# PC.net
KiCad netlist of a schematic drawn in EAGLE
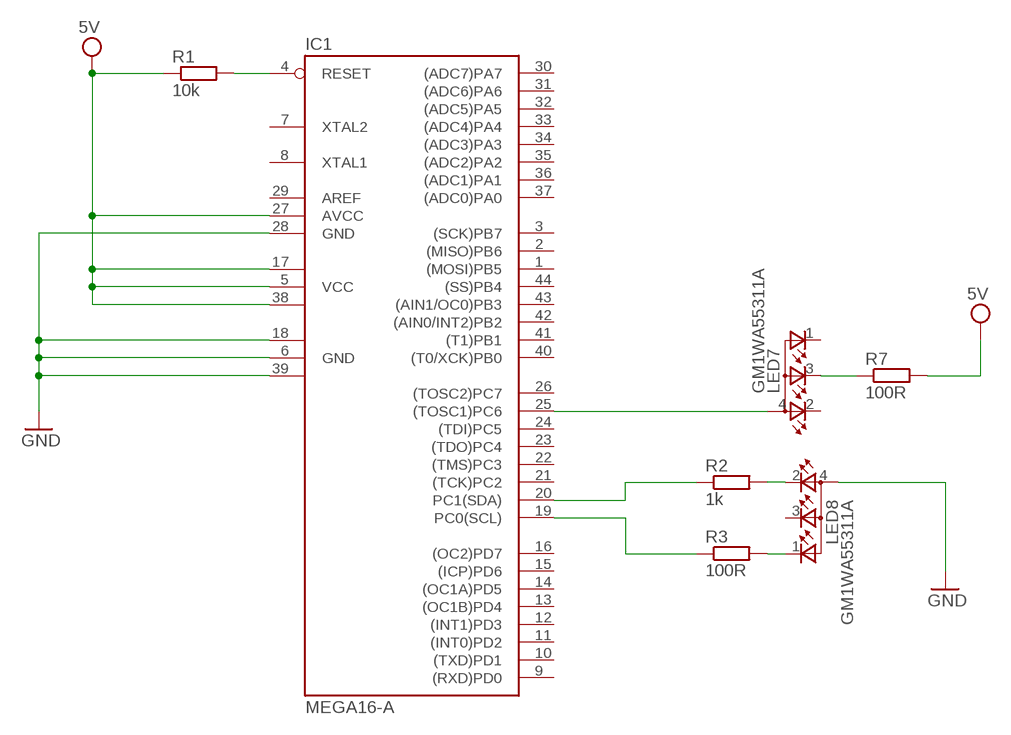
[diagram p0: schematic, sheet 1]

(export (version "E")
  (design (tool "Eeschema 10.0.6"))
  (components
    (comp (ref "IC1")
      (value "MEGA16-A")
      (footprint "eagle-import:TQFP44")
      (fields (field (name "MPN") "ATMEGA16-16AU"))
      (libsource (lib "eagle-import") (part "MEGA16-A"))
    )
    (comp (ref "LED7")
      (value "GM1WA55311A")
      (footprint "eagle-import:GM1WA55311A")
      (libsource (lib "eagle-import") (part "GM1WA55311A"))
    )
    (comp (ref "LED8")
      (value "GM1WA55311A")
      (footprint "eagle-import:GM1WA55311A")
      (libsource (lib "eagle-import") (part "GM1WA55311A"))
    )
    (comp (ref "R1")
      (value "10k")
      (footprint "eagle-import:M0805")
      (libsource (lib "eagle-import") (part "R-EU_M0805"))
    )
    (comp (ref "R2")
      (value "1k")
      (footprint "eagle-import:M0805")
      (libsource (lib "eagle-import") (part "R-EU_M0805"))
    )
    (comp (ref "R3")
      (value "100R")
      (footprint "eagle-import:M0805")
      (libsource (lib "eagle-import") (part "R-EU_M0805"))
    )
    (comp (ref "R7")
      (value "100R")
      (footprint "eagle-import:M0805")
      (libsource (lib "eagle-import") (part "R-EU_M0805"))
    )
  )
  (nets
    (net (code "1") (name "5V") (class "Default")
      (node (ref "IC1") (pin "17") (pinfunction "VCC1_17") (pintype "power_in"))
      (node (ref "IC1") (pin "27") (pinfunction "AVCC_27") (pintype "power_in"))
      (node (ref "IC1") (pin "38") (pinfunction "VCC2_38") (pintype "power_in"))
      (node (ref "IC1") (pin "5") (pinfunction "VCC_5") (pintype "power_in"))
      (node (ref "R1") (pin "1") (pinfunction "1_1") (pintype "passive"))
      (node (ref "R7") (pin "2") (pinfunction "2_2") (pintype "passive"))
    )
    (net (code "2") (name "GND") (class "Default")
      (node (ref "IC1") (pin "18") (pinfunction "GND1_18") (pintype "power_in"))
      (node (ref "IC1") (pin "28") (pinfunction "GND_28") (pintype "power_in"))
      (node (ref "IC1") (pin "39") (pinfunction "GND2_39") (pintype "power_in"))
      (node (ref "IC1") (pin "6") (pinfunction "GND_6") (pintype "power_in"))
    )
    (net (code "3") (name "Net-(IC1-(TOSC1)PC6)") (class "Default")
      (node (ref "IC1") (pin "25") (pinfunction "(TOSC1)PC6_25") (pintype "bidirectional"))
      (node (ref "LED7") (pin "4") (pinfunction "A_4") (pintype "passive"))
    )
    (net (code "4") (name "Net-(IC1-PC0(SCL))") (class "Default")
      (node (ref "IC1") (pin "19") (pinfunction "PC0(SCL)_19") (pintype "bidirectional"))
      (node (ref "R3") (pin "1") (pinfunction "1_1") (pintype "passive"))
    )
    (net (code "5") (name "Net-(IC1-PC1(SDA))") (class "Default")
      (node (ref "IC1") (pin "20") (pinfunction "PC1(SDA)_20") (pintype "bidirectional"))
      (node (ref "R2") (pin "1") (pinfunction "1_1") (pintype "passive"))
    )
    (net (code "6") (name "Net-(IC1-RESET)") (class "Default")
      (node (ref "IC1") (pin "4") (pinfunction "RESET_4") (pintype "input"))
      (node (ref "R1") (pin "2") (pinfunction "2_2") (pintype "passive"))
    )
    (net (code "7") (name "Net-(LED7-CBLUE)") (class "Default")
      (node (ref "LED7") (pin "3") (pinfunction "CBLUE_3") (pintype "passive"))
      (node (ref "R7") (pin "1") (pinfunction "1_1") (pintype "passive"))
    )
    (net (code "8") (name "Net-(LED8-CGREEN)") (class "Default")
      (node (ref "LED8") (pin "1") (pinfunction "CGREEN_1") (pintype "passive"))
      (node (ref "R3") (pin "2") (pinfunction "2_2") (pintype "passive"))
    )
    (net (code "9") (name "Net-(LED8-CRED)") (class "Default")
      (node (ref "LED8") (pin "2") (pinfunction "CRED_2") (pintype "passive"))
      (node (ref "R2") (pin "2") (pinfunction "2_2") (pintype "passive"))
    )
    (net (code "10") (name "unconnected-(IC1-(ADC0)PA0-Pad37)") (class "Default")
      (node (ref "IC1") (pin "37") (pinfunction "(ADC0)PA0_37") (pintype "bidirectional"))
    )
    (net (code "11") (name "unconnected-(IC1-(ADC1)PA1-Pad36)") (class "Default")
      (node (ref "IC1") (pin "36") (pinfunction "(ADC1)PA1_36") (pintype "bidirectional"))
    )
    (net (code "12") (name "unconnected-(IC1-(ADC2)PA2-Pad35)") (class "Default")
      (node (ref "IC1") (pin "35") (pinfunction "(ADC2)PA2_35") (pintype "bidirectional"))
    )
    (net (code "13") (name "unconnected-(IC1-(ADC3)PA3-Pad34)") (class "Default")
      (node (ref "IC1") (pin "34") (pinfunction "(ADC3)PA3_34") (pintype "bidirectional"))
    )
    (net (code "14") (name "unconnected-(IC1-(ADC4)PA4-Pad33)") (class "Default")
      (node (ref "IC1") (pin "33") (pinfunction "(ADC4)PA4_33") (pintype "bidirectional"))
    )
    (net (code "15") (name "unconnected-(IC1-(ADC5)PA5-Pad32)") (class "Default")
      (node (ref "IC1") (pin "32") (pinfunction "(ADC5)PA5_32") (pintype "bidirectional"))
    )
    (net (code "16") (name "unconnected-(IC1-(ADC6)PA6-Pad31)") (class "Default")
      (node (ref "IC1") (pin "31") (pinfunction "(ADC6)PA6_31") (pintype "bidirectional"))
    )
    (net (code "17") (name "unconnected-(IC1-(ADC7)PA7-Pad30)") (class "Default")
      (node (ref "IC1") (pin "30") (pinfunction "(ADC7)PA7_30") (pintype "bidirectional"))
    )
    (net (code "18") (name "unconnected-(IC1-(AIN0{slash}INT2)PB2-Pad42)") (class "Default")
      (node (ref "IC1") (pin "42") (pinfunction "(AIN0/INT2)PB2_42") (pintype "bidirectional"))
    )
    (net (code "19") (name "unconnected-(IC1-(AIN1{slash}OC0)PB3-Pad43)") (class "Default")
      (node (ref "IC1") (pin "43") (pinfunction "(AIN1/OC0)PB3_43") (pintype "bidirectional"))
    )
    (net (code "20") (name "unconnected-(IC1-(ICP)PD6-Pad15)") (class "Default")
      (node (ref "IC1") (pin "15") (pinfunction "(ICP)PD6_15") (pintype "bidirectional"))
    )
    (net (code "21") (name "unconnected-(IC1-(INT0)PD2-Pad11)") (class "Default")
      (node (ref "IC1") (pin "11") (pinfunction "(INT0)PD2_11") (pintype "bidirectional"))
    )
    (net (code "22") (name "unconnected-(IC1-(INT1)PD3-Pad12)") (class "Default")
      (node (ref "IC1") (pin "12") (pinfunction "(INT1)PD3_12") (pintype "bidirectional"))
    )
    (net (code "23") (name "unconnected-(IC1-(MISO)PB6-Pad2)") (class "Default")
      (node (ref "IC1") (pin "2") (pinfunction "(MISO)PB6_2") (pintype "bidirectional"))
    )
    (net (code "24") (name "unconnected-(IC1-(MOSI)PB5-Pad1)") (class "Default")
      (node (ref "IC1") (pin "1") (pinfunction "(MOSI)PB5_1") (pintype "bidirectional"))
    )
    (net (code "25") (name "unconnected-(IC1-(OC1A)PD5-Pad14)") (class "Default")
      (node (ref "IC1") (pin "14") (pinfunction "(OC1A)PD5_14") (pintype "bidirectional"))
    )
    (net (code "26") (name "unconnected-(IC1-(OC1B)PD4-Pad13)") (class "Default")
      (node (ref "IC1") (pin "13") (pinfunction "(OC1B)PD4_13") (pintype "bidirectional"))
    )
    (net (code "27") (name "unconnected-(IC1-(OC2)PD7-Pad16)") (class "Default")
      (node (ref "IC1") (pin "16") (pinfunction "(OC2)PD7_16") (pintype "bidirectional"))
    )
    (net (code "28") (name "unconnected-(IC1-(RXD)PD0-Pad9)") (class "Default")
      (node (ref "IC1") (pin "9") (pinfunction "(RXD)PD0_9") (pintype "bidirectional"))
    )
    (net (code "29") (name "unconnected-(IC1-(SCK)PB7-Pad3)") (class "Default")
      (node (ref "IC1") (pin "3") (pinfunction "(SCK)PB7_3") (pintype "bidirectional"))
    )
    (net (code "30") (name "unconnected-(IC1-(SS)PB4-Pad44)") (class "Default")
      (node (ref "IC1") (pin "44") (pinfunction "(SS)PB4_44") (pintype "bidirectional"))
    )
    (net (code "31") (name "unconnected-(IC1-(T0{slash}XCK)PB0-Pad40)") (class "Default")
      (node (ref "IC1") (pin "40") (pinfunction "(T0/XCK)PB0_40") (pintype "bidirectional"))
    )
    (net (code "32") (name "unconnected-(IC1-(T1)PB1-Pad41)") (class "Default")
      (node (ref "IC1") (pin "41") (pinfunction "(T1)PB1_41") (pintype "bidirectional"))
    )
    (net (code "33") (name "unconnected-(IC1-(TCK)PC2-Pad21)") (class "Default")
      (node (ref "IC1") (pin "21") (pinfunction "(TCK)PC2_21") (pintype "bidirectional"))
    )
    (net (code "34") (name "unconnected-(IC1-(TDI)PC5-Pad24)") (class "Default")
      (node (ref "IC1") (pin "24") (pinfunction "(TDI)PC5_24") (pintype "bidirectional"))
    )
    (net (code "35") (name "unconnected-(IC1-(TDO)PC4-Pad23)") (class "Default")
      (node (ref "IC1") (pin "23") (pinfunction "(TDO)PC4_23") (pintype "bidirectional"))
    )
    (net (code "36") (name "unconnected-(IC1-(TMS)PC3-Pad22)") (class "Default")
      (node (ref "IC1") (pin "22") (pinfunction "(TMS)PC3_22") (pintype "bidirectional"))
    )
    (net (code "37") (name "unconnected-(IC1-(TOSC2)PC7-Pad26)") (class "Default")
      (node (ref "IC1") (pin "26") (pinfunction "(TOSC2)PC7_26") (pintype "bidirectional"))
    )
    (net (code "38") (name "unconnected-(IC1-(TXD)PD1-Pad10)") (class "Default")
      (node (ref "IC1") (pin "10") (pinfunction "(TXD)PD1_10") (pintype "bidirectional"))
    )
    (net (code "39") (name "unconnected-(IC1-AREF-Pad29)") (class "Default")
      (node (ref "IC1") (pin "29") (pinfunction "AREF_29") (pintype "passive"))
    )
    (net (code "40") (name "unconnected-(IC1-XTAL1-Pad8)") (class "Default")
      (node (ref "IC1") (pin "8") (pinfunction "XTAL1_8") (pintype "bidirectional"))
    )
    (net (code "41") (name "unconnected-(IC1-XTAL2-Pad7)") (class "Default")
      (node (ref "IC1") (pin "7") (pinfunction "XTAL2_7") (pintype "bidirectional"))
    )
    (net (code "42") (name "unconnected-(LED7-CGREEN-Pad1)") (class "Default")
      (node (ref "LED7") (pin "1") (pinfunction "CGREEN_1") (pintype "passive"))
    )
    (net (code "43") (name "unconnected-(LED7-CRED-Pad2)") (class "Default")
      (node (ref "LED7") (pin "2") (pinfunction "CRED_2") (pintype "passive"))
    )
    (net (code "44") (name "unconnected-(LED8-A-Pad4)") (class "Default")
      (node (ref "LED8") (pin "4") (pinfunction "A_4") (pintype "passive"))
    )
    (net (code "45") (name "unconnected-(LED8-CBLUE-Pad3)") (class "Default")
      (node (ref "LED8") (pin "3") (pinfunction "CBLUE_3") (pintype "passive"))
    )
  )
)
